# Supply.net
KiCad netlist of a schematic drawn in Altium Designer
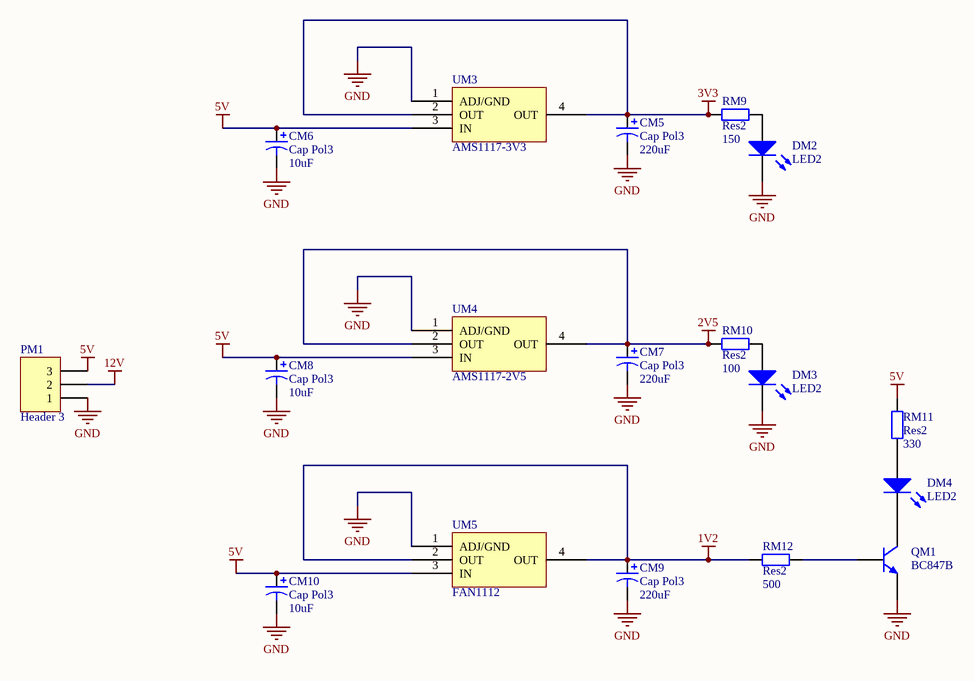
[diagram p0: Supply.SchDoc]

(export (version "E")
  (design (tool "Eeschema 10.0.6"))
  (components
    (comp (ref "CM5")
      (value "Cap Pol3")
      (footprint "SIZE D")
      (description "Polarized Capacitor (Surface Mount)")
      (fields (field (name "ALTIUM_VALUE") "220uF") (field (name "PUBLISHER") "Altium Limited"))
      (libsource (lib "Miscellaneous Devices") (part "Cap Pol3"))
    )
    (comp (ref "CM6")
      (value "Cap Pol3")
      (footprint "SIZE B")
      (description "Polarized Capacitor (Surface Mount)")
      (fields (field (name "ALTIUM_VALUE") "10uF") (field (name "PUBLISHER") "Altium Limited"))
      (libsource (lib "Miscellaneous Devices") (part "Cap Pol3"))
    )
    (comp (ref "CM7")
      (value "Cap Pol3")
      (footprint "SIZE D")
      (description "Polarized Capacitor (Surface Mount)")
      (fields (field (name "ALTIUM_VALUE") "220uF") (field (name "PUBLISHER") "Altium Limited"))
      (libsource (lib "Miscellaneous Devices") (part "Cap Pol3"))
    )
    (comp (ref "CM8")
      (value "Cap Pol3")
      (footprint "SIZE B")
      (description "Polarized Capacitor (Surface Mount)")
      (fields (field (name "ALTIUM_VALUE") "10uF") (field (name "PUBLISHER") "Altium Limited"))
      (libsource (lib "Miscellaneous Devices") (part "Cap Pol3"))
    )
    (comp (ref "CM9")
      (value "Cap Pol3")
      (footprint "SIZE D")
      (description "Polarized Capacitor (Surface Mount)")
      (fields (field (name "ALTIUM_VALUE") "220uF") (field (name "PUBLISHER") "Altium Limited"))
      (libsource (lib "Miscellaneous Devices") (part "Cap Pol3"))
    )
    (comp (ref "CM10")
      (value "Cap Pol3")
      (footprint "SIZE B")
      (description "Polarized Capacitor (Surface Mount)")
      (fields (field (name "ALTIUM_VALUE") "10uF") (field (name "PUBLISHER") "Altium Limited"))
      (libsource (lib "Miscellaneous Devices") (part "Cap Pol3"))
    )
    (comp (ref "DM2")
      (value "LED2")
      (footprint "3.2X1.6X1.1")
      (description "Typical RED, GREEN, YELLOW, AMBER GaAs LED")
      (fields (field (name "PUBLISHER") "Altium Limited"))
      (libsource (lib "Miscellaneous Devices") (part "LED2"))
    )
    (comp (ref "DM3")
      (value "LED2")
      (footprint "3.2X1.6X1.1")
      (description "Typical RED, GREEN, YELLOW, AMBER GaAs LED")
      (fields (field (name "PUBLISHER") "Altium Limited"))
      (libsource (lib "Miscellaneous Devices") (part "LED2"))
    )
    (comp (ref "DM4")
      (value "LED2")
      (footprint "3.2X1.6X1.1")
      (description "Typical RED, GREEN, YELLOW, AMBER GaAs LED")
      (fields (field (name "PUBLISHER") "Altium Limited"))
      (libsource (lib "Miscellaneous Devices") (part "LED2"))
    )
    (comp (ref "PM1")
      (value "Header 3")
      (footprint "HDR1X3")
      (description "Header, 3-Pin")
      (fields (field (name "PUBLISHER") "Altium Limited"))
      (libsource (lib "Miscellaneous Connectors") (part "Header 3"))
    )
    (comp (ref "QM1")
      (value "BC847B")
      (footprint "SOT23_M")
      (description "NPN Bipolar Transistor")
      (fields (field (name "PUBLISHER") "Altium Limited"))
      (libsource (lib "Miscellaneous Devices") (part "NPN"))
    )
    (comp (ref "RM9")
      (value "Res2")
      (footprint "6-0805_N")
      (description "Resistor")
      (fields (field (name "ALTIUM_VALUE") "150") (field (name "PUBLISHER") "Altium Limited"))
      (libsource (lib "Miscellaneous Devices") (part "Res2"))
    )
    (comp (ref "RM10")
      (value "Res2")
      (footprint "6-0805_N")
      (description "Resistor")
      (fields (field (name "ALTIUM_VALUE") "100") (field (name "PUBLISHER") "Altium Limited"))
      (libsource (lib "Miscellaneous Devices") (part "Res2"))
    )
    (comp (ref "RM11")
      (value "Res2")
      (footprint "6-0805_N")
      (description "Resistor")
      (fields (field (name "ALTIUM_VALUE") "330") (field (name "PUBLISHER") "Altium Limited"))
      (libsource (lib "") (part "Res2_1"))
    )
    (comp (ref "RM12")
      (value "Res2")
      (footprint "6-0805_N")
      (description "Resistor")
      (fields (field (name "ALTIUM_VALUE") "500") (field (name "PUBLISHER") "Altium Limited"))
      (libsource (lib "Miscellaneous Devices") (part "Res2"))
    )
    (comp (ref "UM3")
      (value "AMS1117-3V3")
      (footprint "TO-252")
      (libsource (lib "YavandLIB") (part "AMS1117-3.3V"))
    )
    (comp (ref "UM4")
      (value "AMS1117-2V5")
      (footprint "TO-252")
      (libsource (lib "YavandLIB") (part "AMS1117-3.3V"))
    )
    (comp (ref "UM5")
      (value "FAN1112")
      (footprint "TO-252")
      (libsource (lib "YavandLIB") (part "AMS1117-3.3V"))
    )
  )
  (nets
    (net (code "1") (name "1V2") (class "Default")
      (node (ref "CM9") (pin "1") (pinfunction "1_1") (pintype "passive"))
      (node (ref "RM12") (pin "1") (pinfunction "1_1") (pintype "passive"))
      (node (ref "UM5") (pin "2") (pinfunction "OUT_2") (pintype "passive"))
      (node (ref "UM5") (pin "4") (pinfunction "OUT_4") (pintype "passive"))
    )
    (net (code "2") (name "2V5") (class "Default")
      (node (ref "CM7") (pin "1") (pinfunction "1_1") (pintype "passive"))
      (node (ref "RM10") (pin "1") (pinfunction "1_1") (pintype "passive"))
      (node (ref "UM4") (pin "2") (pinfunction "OUT_2") (pintype "passive"))
      (node (ref "UM4") (pin "4") (pinfunction "OUT_4") (pintype "passive"))
    )
    (net (code "3") (name "3V3") (class "Default")
      (node (ref "CM5") (pin "1") (pinfunction "1_1") (pintype "passive"))
      (node (ref "RM9") (pin "1") (pinfunction "1_1") (pintype "passive"))
      (node (ref "UM3") (pin "2") (pinfunction "OUT_2") (pintype "passive"))
      (node (ref "UM3") (pin "4") (pinfunction "OUT_4") (pintype "passive"))
    )
    (net (code "4") (name "5V") (class "Default")
      (node (ref "CM10") (pin "1") (pinfunction "1_1") (pintype "passive"))
      (node (ref "CM6") (pin "1") (pinfunction "1_1") (pintype "passive"))
      (node (ref "CM8") (pin "1") (pinfunction "1_1") (pintype "passive"))
      (node (ref "PM1") (pin "3") (pinfunction "3_3") (pintype "passive"))
      (node (ref "RM11") (pin "2") (pinfunction "2_2") (pintype "passive"))
      (node (ref "UM3") (pin "3") (pinfunction "IN_3") (pintype "passive"))
      (node (ref "UM4") (pin "3") (pinfunction "IN_3") (pintype "passive"))
      (node (ref "UM5") (pin "3") (pinfunction "IN_3") (pintype "passive"))
    )
    (net (code "5") (name "12V") (class "Default")
      (node (ref "PM1") (pin "2") (pinfunction "2_2") (pintype "passive"))
    )
    (net (code "6") (name "GND") (class "Default")
      (node (ref "CM10") (pin "2") (pinfunction "2_2") (pintype "passive"))
      (node (ref "CM5") (pin "2") (pinfunction "2_2") (pintype "passive"))
      (node (ref "CM6") (pin "2") (pinfunction "2_2") (pintype "passive"))
      (node (ref "CM7") (pin "2") (pinfunction "2_2") (pintype "passive"))
      (node (ref "CM8") (pin "2") (pinfunction "2_2") (pintype "passive"))
      (node (ref "CM9") (pin "2") (pinfunction "2_2") (pintype "passive"))
      (node (ref "DM2") (pin "2") (pinfunction "K_2") (pintype "passive"))
      (node (ref "DM3") (pin "2") (pinfunction "K_2") (pintype "passive"))
      (node (ref "PM1") (pin "1") (pinfunction "1_1") (pintype "passive"))
      (node (ref "QM1") (pin "3") (pinfunction "E_3") (pintype "passive"))
      (node (ref "UM3") (pin "1") (pinfunction "ADJ/GND_1") (pintype "passive"))
      (node (ref "UM4") (pin "1") (pinfunction "ADJ/GND_1") (pintype "passive"))
      (node (ref "UM5") (pin "1") (pinfunction "ADJ/GND_1") (pintype "passive"))
    )
    (net (code "7") (name "Net-(DM2-A)") (class "Default")
      (node (ref "DM2") (pin "1") (pinfunction "A_1") (pintype "passive"))
      (node (ref "RM9") (pin "2") (pinfunction "2_2") (pintype "passive"))
    )
    (net (code "8") (name "Net-(DM3-A)") (class "Default")
      (node (ref "DM3") (pin "1") (pinfunction "A_1") (pintype "passive"))
      (node (ref "RM10") (pin "2") (pinfunction "2_2") (pintype "passive"))
    )
    (net (code "9") (name "Net-(DM4-A)") (class "Default")
      (node (ref "DM4") (pin "1") (pinfunction "A_1") (pintype "passive"))
      (node (ref "RM11") (pin "1") (pinfunction "1_1") (pintype "passive"))
    )
    (net (code "10") (name "Net-(DM4-K)") (class "Default")
      (node (ref "DM4") (pin "2") (pinfunction "K_2") (pintype "passive"))
      (node (ref "QM1") (pin "1") (pinfunction "C_1") (pintype "passive"))
    )
    (net (code "11") (name "Net-(QM1-B)") (class "Default")
      (node (ref "QM1") (pin "2") (pinfunction "B_2") (pintype "passive"))
      (node (ref "RM12") (pin "2") (pinfunction "2_2") (pintype "passive"))
    )
  )
)
